# Scout-EasyEDA.net
KiCad netlist of a schematic drawn in EasyEDA
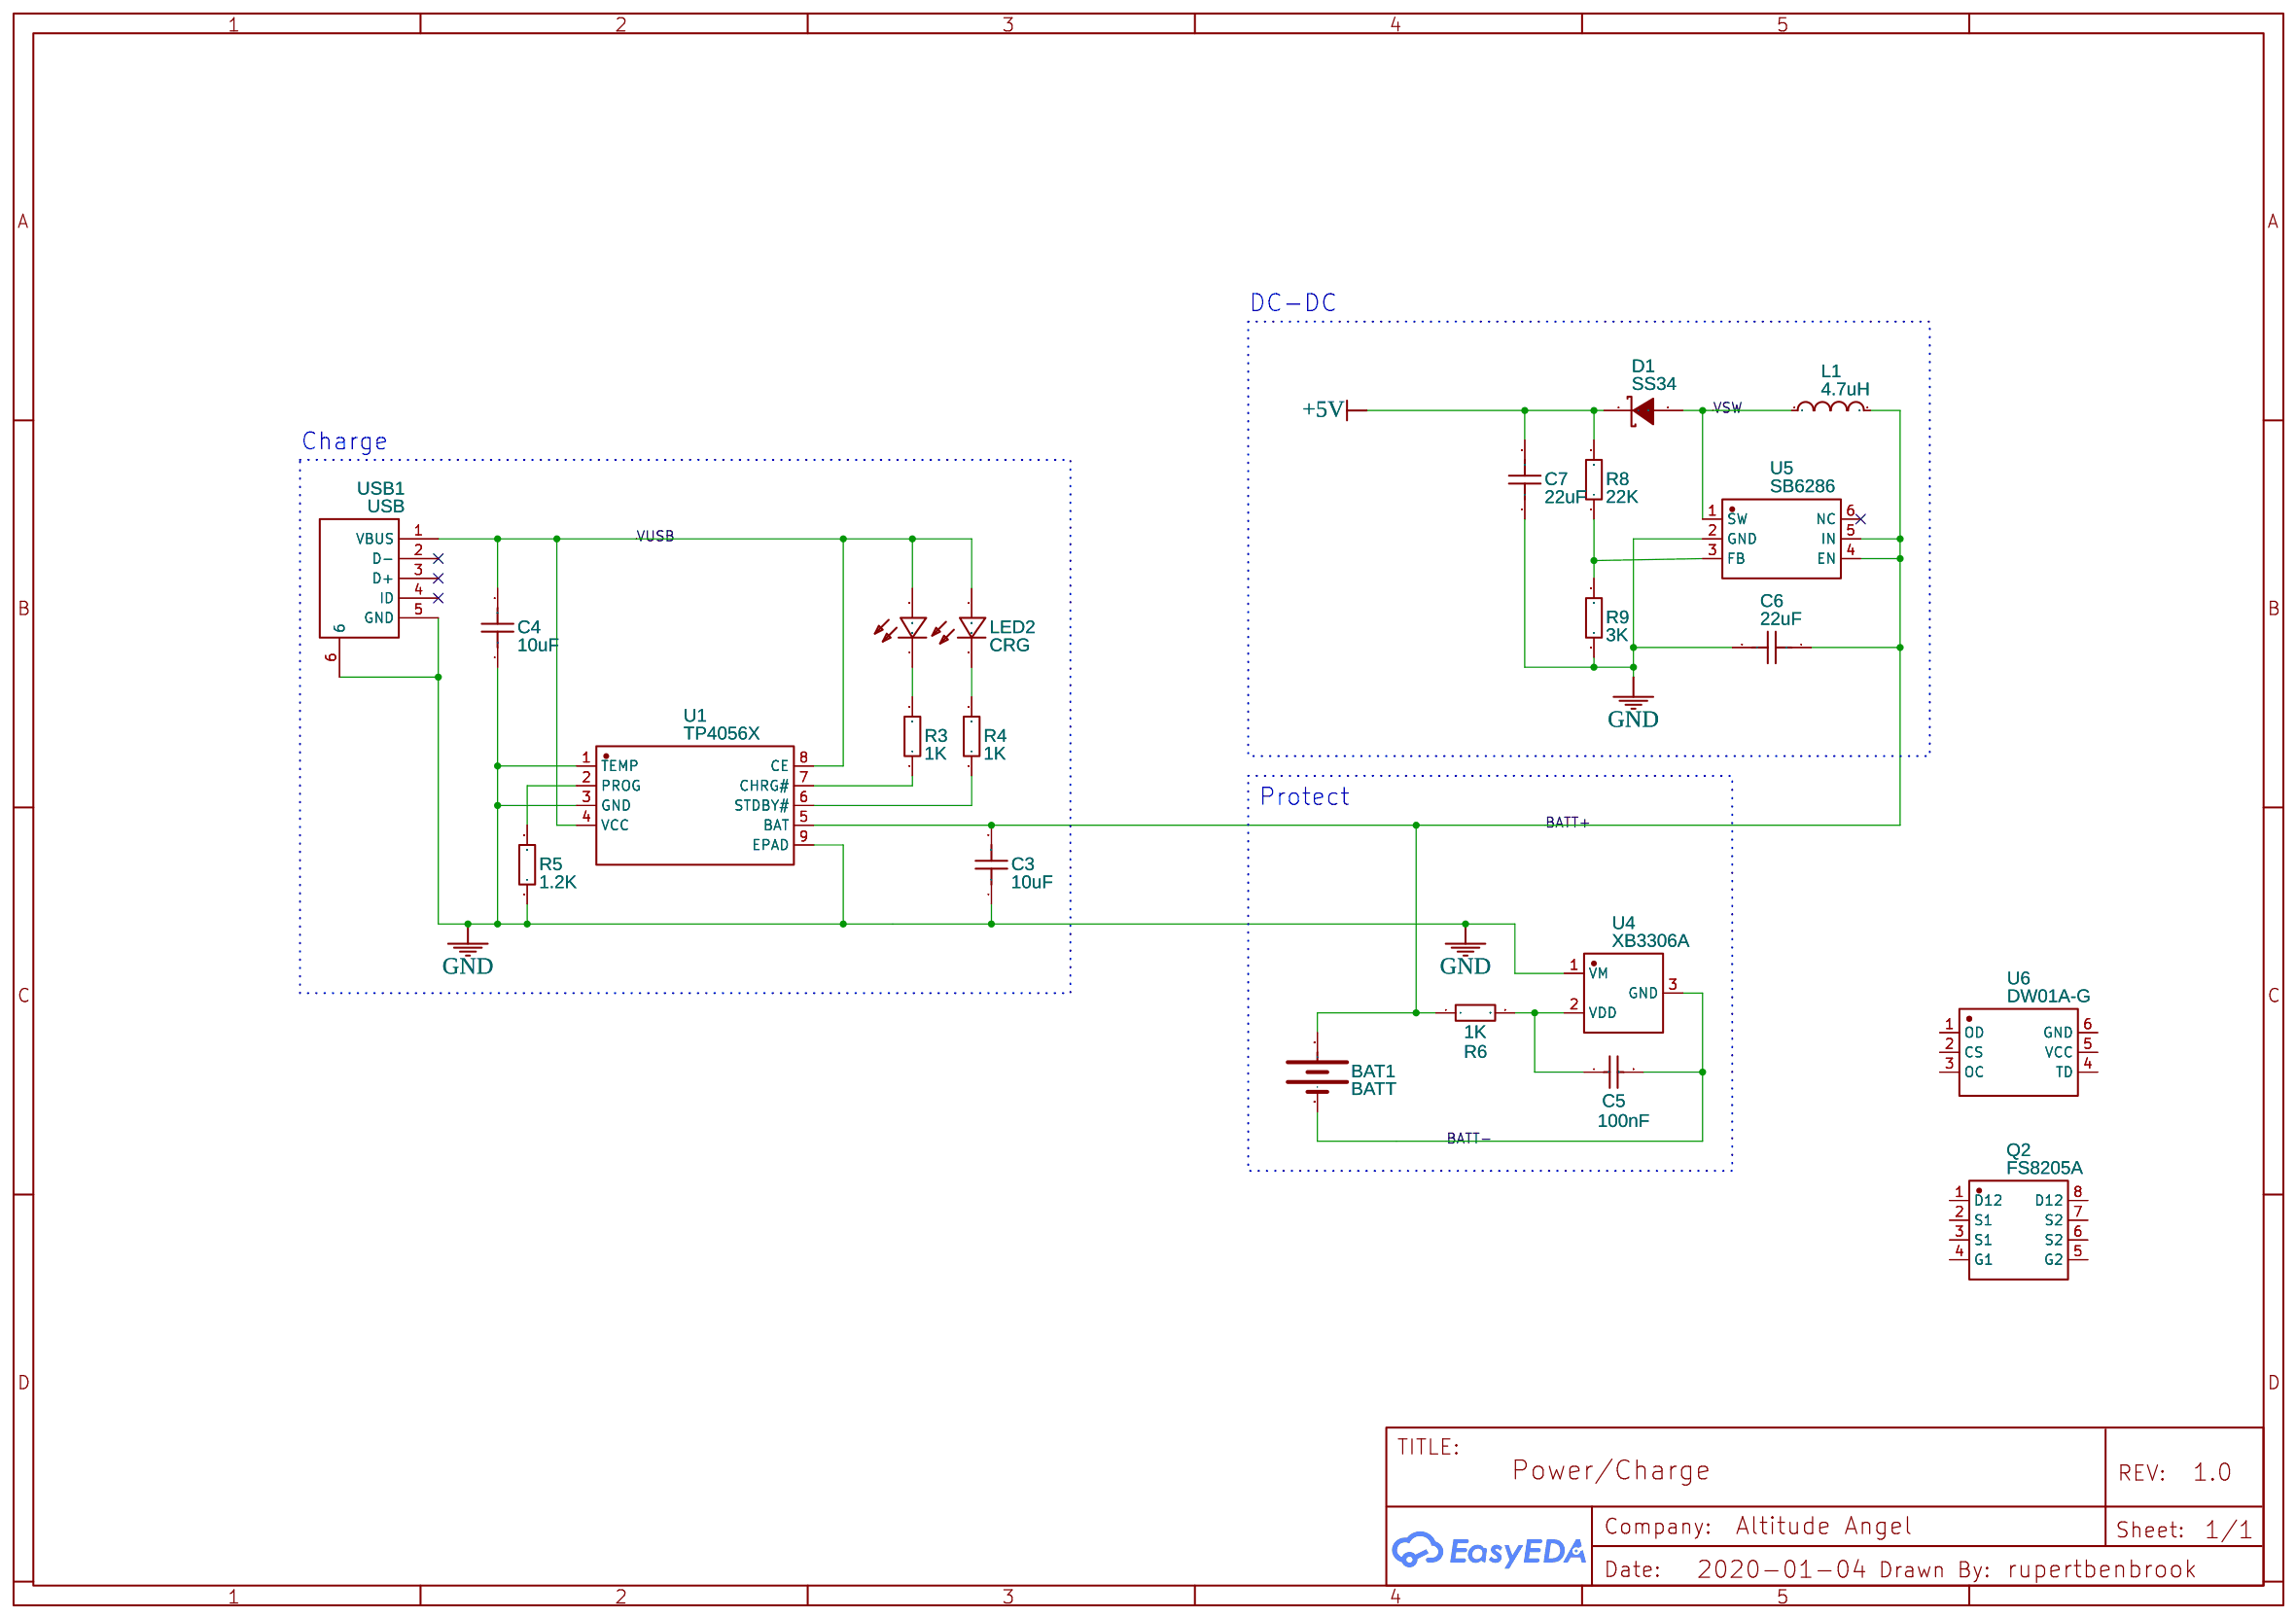
[diagram p0: Power-Charge]
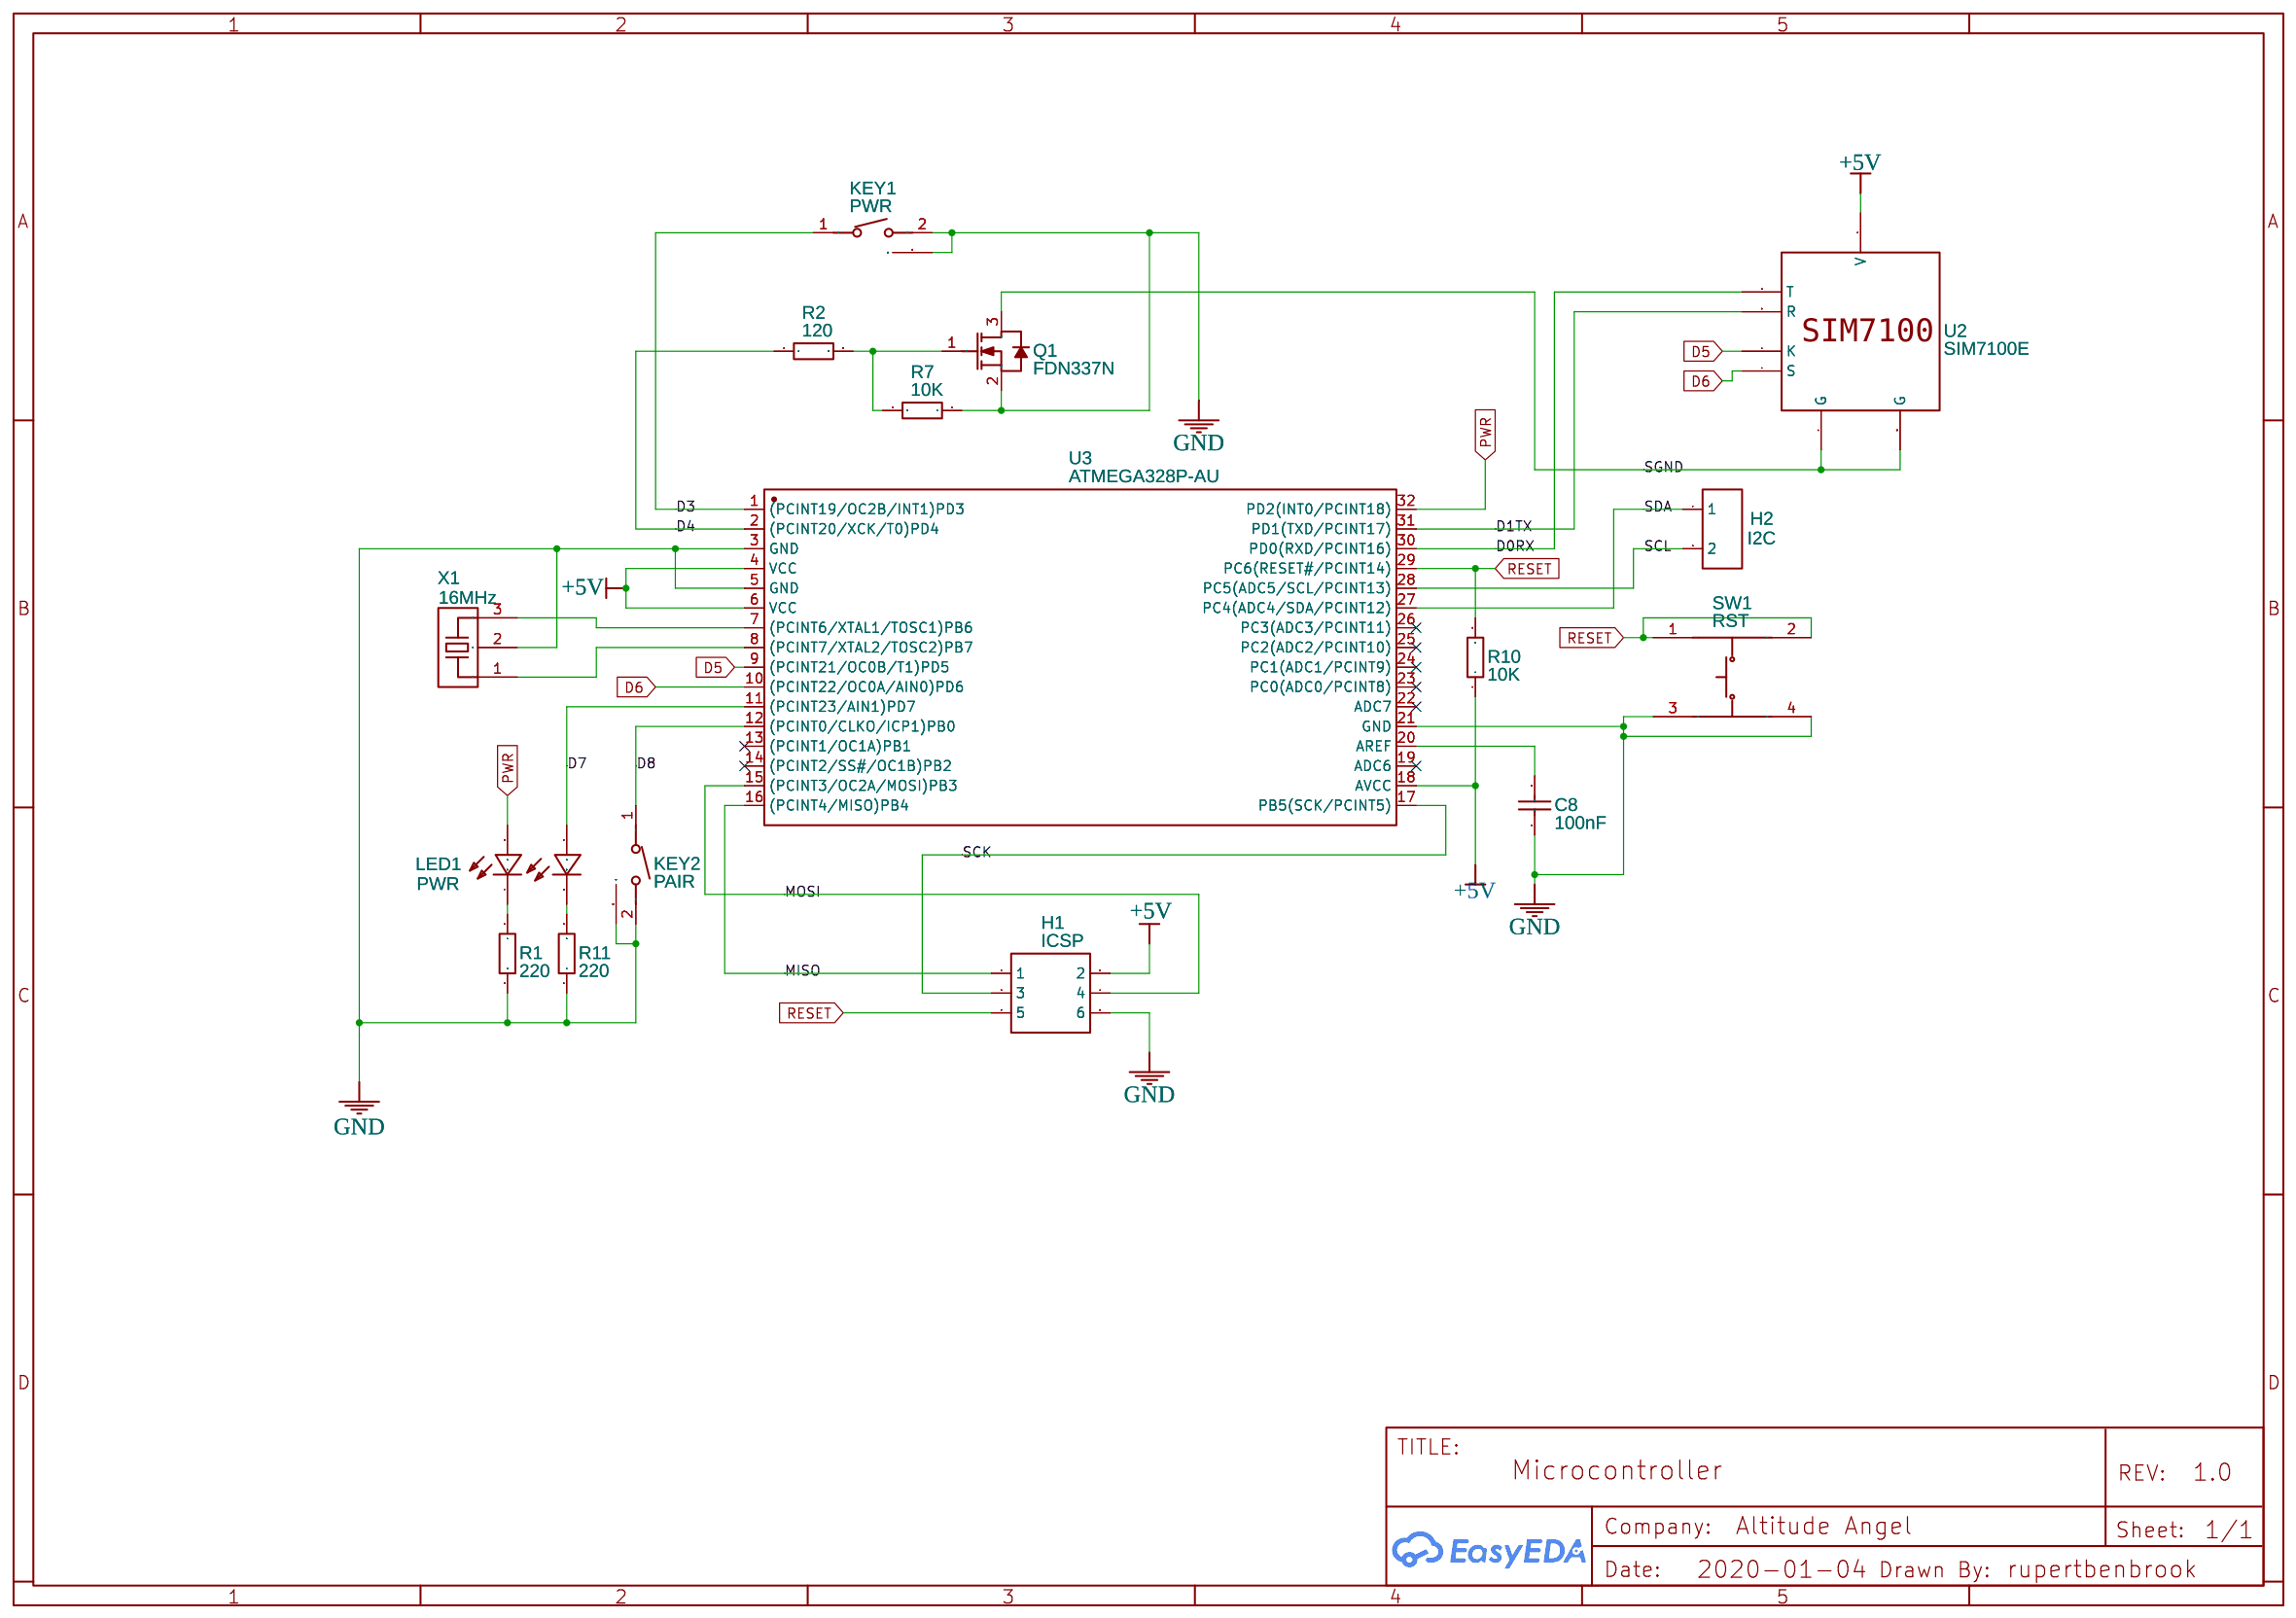
[diagram p1: Microcontroller]

(export (version "E")
  (design (tool "Eeschema 10.0.6"))
  (components
    (comp (ref "BAT1") (value "BATT") (libsource (lib "") (part "BATTERY18650")))
    (comp (ref "C3")
      (value "10uF")
      (fields
        (field (name "BOM_Manufacturer Part") "GRM188R61A106KE69D")
        (field (name "BOM_Supplier Part") "C77044")
      )
      (libsource (lib "") (part "GRM188R61A106KE69D"))
    )
    (comp (ref "C4")
      (value "10uF")
      (fields
        (field (name "BOM_Manufacturer Part") "GRM188R61A106KE69D")
        (field (name "BOM_Supplier Part") "C77044")
      )
      (libsource (lib "") (part "GRM188R61A106KE69D"))
    )
    (comp (ref "C5")
      (value "100nF")
      (fields
        (field (name "BOM_Manufacturer Part") "GRM188R71C104KA01D")
        (field (name "BOM_Supplier Part") "C45000")
      )
      (libsource (lib "") (part "GRM188R71C104KA01D"))
    )
    (comp (ref "C6")
      (value "22uF")
      (fields
        (field (name "BOM_Manufacturer Part") "GRM188R61A226ME15D")
        (field (name "BOM_Supplier Part") "C84419")
      )
      (libsource (lib "") (part "GRM188R61A226ME15D_1"))
    )
    (comp (ref "C7")
      (value "22uF")
      (fields
        (field (name "BOM_Manufacturer Part") "GRM188R61A226ME15D")
        (field (name "BOM_Supplier Part") "C84419")
      )
      (libsource (lib "") (part "GRM188R61A226ME15D"))
    )
    (comp (ref "D1")
      (value "SS34")
      (fields (field (name "BOM_Supplier Part") "C13762"))
      (libsource (lib "") (part "SS34_C13762"))
    )
    (comp (ref "L1")
      (value "4.7uH")
      (fields
        (field (name "BOM_Manufacturer Part") "LQH5BPN4R7NT0L")
        (field (name "BOM_Supplier Part") "C171792")
      )
      (libsource (lib "") (part "LQH5BPN4R7NT0L"))
    )
    (comp (ref "LED2")
      (value "CRG")
      (fields
        (field (name "BOM_Manufacturer Part") "LTST-C195KGJRKT")
        (field (name "BOM_Supplier Part") "C125104")
      )
      (libsource (lib "") (part "LTST-C195KGJRKT"))
    )
    (comp (ref "Q2")
      (value "FS8205A")
      (fields (field (name "BOM_Supplier Part") "C16052"))
      (libsource (lib "") (part "FS8205A"))
    )
    (comp (ref "R3")
      (value "1K")
      (fields
        (field (name "BOM_Manufacturer Part") "RTT031001FTP")
        (field (name "BOM_Supplier Part") "C103198")
      )
      (libsource (lib "") (part "RTT031001FTP"))
    )
    (comp (ref "R4")
      (value "1K")
      (fields
        (field (name "BOM_Manufacturer Part") "RTT031001FTP")
        (field (name "BOM_Supplier Part") "C103198")
      )
      (libsource (lib "") (part "RTT031001FTP"))
    )
    (comp (ref "R5")
      (value "1.2K")
      (fields
        (field (name "BOM_Manufacturer Part") "RTT031201FTP")
        (field (name "BOM_Supplier Part") "C103248")
      )
      (libsource (lib "") (part "RTT031201FTP"))
    )
    (comp (ref "R6")
      (value "1K")
      (fields
        (field (name "BOM_Manufacturer Part") "RTT031001FTP")
        (field (name "BOM_Supplier Part") "C103198")
      )
      (libsource (lib "") (part "RTT031001FTP_1"))
    )
    (comp (ref "R8")
      (value "22K")
      (fields
        (field (name "BOM_Manufacturer Part") "RTT032202FTP")
        (field (name "BOM_Supplier Part") "C103416")
      )
      (libsource (lib "") (part "RTT032202FTP"))
    )
    (comp (ref "R9")
      (value "3K")
      (fields
        (field (name "BOM_Manufacturer Part") "RTT033001FTP")
        (field (name "BOM_Supplier Part") "C103514")
      )
      (libsource (lib "") (part "RTT033001FTP"))
    )
    (comp (ref "U1")
      (value "TP4056X")
      (fields (field (name "BOM_Supplier Part") "C191323"))
      (libsource (lib "") (part "TP4056X"))
    )
    (comp (ref "U4")
      (value "XB3306A")
      (fields (field (name "BOM_Supplier Part") "C154939"))
      (libsource (lib "") (part "XB3306A"))
    )
    (comp (ref "U5")
      (value "SB6286")
      (fields (field (name "BOM_Supplier Part") "C157668"))
      (libsource (lib "") (part "SB6286"))
    )
    (comp (ref "U6")
      (value "DW01A-G")
      (fields (field (name "BOM_Supplier Part") "C61503"))
      (libsource (lib "") (part "DW01A-G"))
    )
    (comp (ref "USB1")
      (value "USB")
      (fields
        (field (name "BOM_Manufacturer Part") "MICRO5.9mmusb")
        (field (name "BOM_Supplier Part") "C393940")
      )
      (libsource (lib "") (part "MICRO5.9MMUSB"))
    )
    (comp (ref "C8")
      (value "100nF")
      (fields
        (field (name "BOM_Manufacturer Part") "GRM188R71C104KA01D")
        (field (name "BOM_Supplier Part") "C45000")
      )
      (libsource (lib "") (part "GRM188R71C104KA01D"))
    )
    (comp (ref "H1")
      (value "ICSP")
      (fields
        (field (name "BOM_Manufacturer Part") "Header-Male-2.54_2x3")
        (field (name "BOM_Supplier Part") "C65114")
      )
      (libsource (lib "") (part "Header-Male-2.54_2x3"))
    )
    (comp (ref "H2")
      (value "I2C")
      (fields (field (name "BOM_Manufacturer Part") "826629-2") (field (name "BOM_Supplier Part") "C86471"))
      (libsource (lib "") (part "Header-Male-2.54_1x2"))
    )
    (comp (ref "KEY1")
      (value "PWR")
      (fields
        (field (name "BOM_Manufacturer Part") "KAN4562-0501C")
        (field (name "BOM_Supplier Part") "C231728")
      )
      (libsource (lib "") (part "KAN4562-0501C_1"))
    )
    (comp (ref "KEY2")
      (value "PAIR")
      (fields
        (field (name "BOM_Manufacturer Part") "KAN4562-0501C")
        (field (name "BOM_Supplier Part") "C231728")
      )
      (libsource (lib "") (part "KAN4562-0501C"))
    )
    (comp (ref "LED1")
      (value "PWR")
      (fields
        (field (name "BOM_Manufacturer Part") "LTST-C195KGJRKT")
        (field (name "BOM_Supplier Part") "C125104")
      )
      (libsource (lib "") (part "LTST-C195KGJRKT"))
    )
    (comp (ref "Q1")
      (value "FDN337N")
      (fields (field (name "BOM_Supplier Part") "C241805"))
      (libsource (lib "") (part "FDN337N"))
    )
    (comp (ref "R1")
      (value "220")
      (fields
        (field (name "BOM_Manufacturer Part") "RTT032200FTP")
        (field (name "BOM_Supplier Part") "C103414")
      )
      (libsource (lib "") (part "RTT032200FTP_1"))
    )
    (comp (ref "R2")
      (value "120")
      (fields
        (field (name "BOM_Manufacturer Part") "RTT031200FTP")
        (field (name "BOM_Supplier Part") "C103247")
      )
      (libsource (lib "") (part "RTT031200FTP"))
    )
    (comp (ref "R7")
      (value "10K")
      (fields
        (field (name "BOM_Manufacturer Part") "RTT031002FTP")
        (field (name "BOM_Supplier Part") "C103199")
      )
      (libsource (lib "") (part "RTT031002FTP_1"))
    )
    (comp (ref "R10")
      (value "10K")
      (fields
        (field (name "BOM_Manufacturer Part") "RTT031002FTP")
        (field (name "BOM_Supplier Part") "C103199")
      )
      (libsource (lib "") (part "RTT031002FTP"))
    )
    (comp (ref "R11")
      (value "220")
      (fields
        (field (name "BOM_Manufacturer Part") "RTT032200FTP")
        (field (name "BOM_Supplier Part") "C103414")
      )
      (libsource (lib "") (part "RTT032200FTP"))
    )
    (comp (ref "SW1")
      (value "RST")
      (fields
        (field (name "BOM_Manufacturer Part") "TS-1177-B-A-B")
        (field (name "BOM_Supplier Part") "C381051")
      )
      (libsource (lib "") (part "TS-1177-B-A-B"))
    )
    (comp (ref "U2")
      (value "SIM7100E")
      (fields (field (name "BOM_Manufacturer Part") "SIM808"))
      (libsource (lib "") (part "SIM7100E"))
    )
    (comp (ref "U3")
      (value "ATMEGA328P-AU")
      (fields (field (name "BOM_Supplier Part") "C14877"))
      (libsource (lib "") (part "ATMEGA328P-AU"))
    )
    (comp (ref "X1")
      (value "16MHz")
      (fields
        (field (name "BOM_Manufacturer Part") "CSTCE16M0V53-R0")
        (field (name "BOM_Supplier Part") "C32180")
      )
      (libsource (lib "") (part "CSTCE16M0V53-R0"))
    )
  )
  (nets
    (net (code "1") (name "+5V") (class "Default")
      (node (ref "C7") (pin "2") (pinfunction "2_2") (pintype "unspecified"))
      (node (ref "D1") (pin "2") (pinfunction "K_2") (pintype "unspecified"))
      (node (ref "H1") (pin "2") (pinfunction "2_2") (pintype "input"))
      (node (ref "R10") (pin "1") (pinfunction "1_1") (pintype "input"))
      (node (ref "R8") (pin "2") (pinfunction "2_2") (pintype "input"))
      (node (ref "U2") (pin "5") (pinfunction "V_5") (pintype "unspecified"))
      (node (ref "U3") (pin "18") (pinfunction "AVCC_18") (pintype "unspecified"))
      (node (ref "U3") (pin "4") (pinfunction "VCC_4") (pintype "unspecified"))
      (node (ref "U3") (pin "6") (pinfunction "VCC_6") (pintype "unspecified"))
    )
    (net (code "2") (name "BATT+") (class "Default")
      (node (ref "BAT1") (pin "PWR") (pinfunction "+_PWR") (pintype "passive"))
      (node (ref "C3") (pin "2") (pinfunction "2_2") (pintype "unspecified"))
      (node (ref "C6") (pin "1") (pinfunction "1_1") (pintype "unspecified"))
      (node (ref "L1") (pin "2") (pinfunction "2_2") (pintype "unspecified"))
      (node (ref "R6") (pin "1") (pinfunction "1_1") (pintype "input"))
      (node (ref "U1") (pin "5") (pinfunction "BAT_5") (pintype "unspecified"))
      (node (ref "U5") (pin "4") (pinfunction "EN_4") (pintype "unspecified"))
      (node (ref "U5") (pin "5") (pinfunction "IN_5") (pintype "unspecified"))
    )
    (net (code "3") (name "BATT-") (class "Default")
      (node (ref "BAT1") (pin "GND") (pinfunction "-_GND") (pintype "passive"))
      (node (ref "C5") (pin "2") (pinfunction "2_2") (pintype "input"))
      (node (ref "U4") (pin "3") (pinfunction "GND_3") (pintype "unspecified"))
    )
    (net (code "4") (name "D0RX") (class "Default")
      (node (ref "U2") (pin "3") (pinfunction "T_3") (pintype "unspecified"))
      (node (ref "U3") (pin "30") (pinfunction "PD0(RXD/PCINT16)_30") (pintype "unspecified"))
    )
    (net (code "5") (name "D1TX") (class "Default")
      (node (ref "U2") (pin "2") (pinfunction "R_2") (pintype "unspecified"))
      (node (ref "U3") (pin "31") (pinfunction "PD1(TXD/PCINT17)_31") (pintype "unspecified"))
    )
    (net (code "6") (name "D3") (class "Default")
      (node (ref "KEY1") (pin "1") (pinfunction "1_1") (pintype "input"))
      (node (ref "U3") (pin "1") (pinfunction "(PCINT19/OC2B/INT1)PD3_1") (pintype "unspecified"))
    )
    (net (code "7") (name "D4") (class "Default")
      (node (ref "R2") (pin "1") (pinfunction "1_1") (pintype "input"))
      (node (ref "U3") (pin "2") (pinfunction "(PCINT20/XCK/T0)PD4_2") (pintype "unspecified"))
    )
    (net (code "8") (name "D5") (class "Default")
      (node (ref "U2") (pin "4") (pinfunction "K_4") (pintype "unspecified"))
      (node (ref "U3") (pin "9") (pinfunction "(PCINT21/OC0B/T1)PD5_9") (pintype "unspecified"))
    )
    (net (code "9") (name "D6") (class "Default")
      (node (ref "U2") (pin "7") (pinfunction "S_7") (pintype "unspecified"))
      (node (ref "U3") (pin "10") (pinfunction "(PCINT22/OC0A/AIN0)PD6_10") (pintype "unspecified"))
    )
    (net (code "10") (name "D7") (class "Default")
      (node (ref "LED1") (pin "1") (pinfunction "G+_1") (pintype "unspecified"))
      (node (ref "U3") (pin "11") (pinfunction "(PCINT23/AIN1)PD7_11") (pintype "unspecified"))
    )
    (net (code "11") (name "D8") (class "Default")
      (node (ref "KEY2") (pin "1") (pinfunction "1_1") (pintype "input"))
      (node (ref "U3") (pin "12") (pinfunction "(PCINT0/CLKO/ICP1)PB0_12") (pintype "unspecified"))
    )
    (net (code "12") (name "GND") (class "Default")
      (node (ref "C3") (pin "1") (pinfunction "1_1") (pintype "unspecified"))
      (node (ref "C4") (pin "1") (pinfunction "1_1") (pintype "unspecified"))
      (node (ref "C6") (pin "2") (pinfunction "2_2") (pintype "unspecified"))
      (node (ref "C7") (pin "1") (pinfunction "1_1") (pintype "unspecified"))
      (node (ref "C8") (pin "1") (pinfunction "1_1") (pintype "input"))
      (node (ref "H1") (pin "6") (pinfunction "6_6") (pintype "input"))
      (node (ref "KEY1") (pin "0") (pinfunction "0_0") (pintype "input"))
      (node (ref "KEY1") (pin "2") (pinfunction "2_2") (pintype "input"))
      (node (ref "KEY2") (pin "0") (pinfunction "0_0") (pintype "input"))
      (node (ref "KEY2") (pin "2") (pinfunction "2_2") (pintype "input"))
      (node (ref "Q1") (pin "2") (pinfunction "S_2") (pintype "unspecified"))
      (node (ref "R1") (pin "2") (pinfunction "2_2") (pintype "input"))
      (node (ref "R11") (pin "1") (pinfunction "1_1") (pintype "input"))
      (node (ref "R5") (pin "1") (pinfunction "1_1") (pintype "input"))
      (node (ref "R7") (pin "1") (pinfunction "1_1") (pintype "input"))
      (node (ref "R9") (pin "1") (pinfunction "1_1") (pintype "input"))
      (node (ref "SW1") (pin "3") (pinfunction "3_3") (pintype "unspecified"))
      (node (ref "SW1") (pin "4") (pinfunction "4_4") (pintype "unspecified"))
      (node (ref "U1") (pin "1") (pinfunction "TEMP_1") (pintype "unspecified"))
      (node (ref "U1") (pin "3") (pinfunction "GND_3") (pintype "unspecified"))
      (node (ref "U1") (pin "9") (pinfunction "EPAD_9") (pintype "unspecified"))
      (node (ref "U3") (pin "21") (pinfunction "GND_21") (pintype "unspecified"))
      (node (ref "U3") (pin "3") (pinfunction "GND_3") (pintype "unspecified"))
      (node (ref "U3") (pin "5") (pinfunction "GND_5") (pintype "unspecified"))
      (node (ref "U4") (pin "1") (pinfunction "VM_1") (pintype "unspecified"))
      (node (ref "U5") (pin "2") (pinfunction "GND_2") (pintype "unspecified"))
      (node (ref "USB1") (pin "5") (pinfunction "GND_5") (pintype "unspecified"))
      (node (ref "USB1") (pin "6") (pinfunction "6_6") (pintype "unspecified"))
      (node (ref "X1") (pin "2") (pinfunction "2_2") (pintype "unspecified"))
    )
    (net (code "13") (name "MISO") (class "Default")
      (node (ref "H1") (pin "1") (pinfunction "1_1") (pintype "input"))
      (node (ref "U3") (pin "16") (pinfunction "(PCINT4/MISO)PB4_16") (pintype "unspecified"))
    )
    (net (code "14") (name "MOSI") (class "Default")
      (node (ref "H1") (pin "4") (pinfunction "4_4") (pintype "input"))
      (node (ref "U3") (pin "15") (pinfunction "(PCINT3/OC2A/MOSI)PB3_15") (pintype "unspecified"))
    )
    (net (code "15") (name "Net-(LED1-G-)") (class "Default")
      (node (ref "LED1") (pin "3") (pinfunction "G-_3") (pintype "unspecified"))
      (node (ref "R11") (pin "2") (pinfunction "2_2") (pintype "input"))
    )
    (net (code "16") (name "Net-(LED1-R-)") (class "Default")
      (node (ref "LED1") (pin "4") (pinfunction "R-_4") (pintype "unspecified"))
      (node (ref "R1") (pin "1") (pinfunction "1_1") (pintype "input"))
    )
    (net (code "17") (name "Net-(LED2-G-)") (class "Default")
      (node (ref "LED2") (pin "3") (pinfunction "G-_3") (pintype "unspecified"))
      (node (ref "R4") (pin "2") (pinfunction "2_2") (pintype "input"))
    )
    (net (code "18") (name "Net-(LED2-R-)") (class "Default")
      (node (ref "LED2") (pin "4") (pinfunction "R-_4") (pintype "unspecified"))
      (node (ref "R3") (pin "2") (pinfunction "2_2") (pintype "input"))
    )
    (net (code "19") (name "Net-(Q1-G)") (class "Default")
      (node (ref "Q1") (pin "1") (pinfunction "G_1") (pintype "unspecified"))
      (node (ref "R2") (pin "2") (pinfunction "2_2") (pintype "input"))
      (node (ref "R7") (pin "2") (pinfunction "2_2") (pintype "input"))
    )
    (net (code "20") (name "Net-(U1-CHRG#)") (class "Default")
      (node (ref "R3") (pin "1") (pinfunction "1_1") (pintype "input"))
      (node (ref "U1") (pin "7") (pinfunction "CHRG#_7") (pintype "unspecified"))
    )
    (net (code "21") (name "Net-(U1-PROG)") (class "Default")
      (node (ref "R5") (pin "2") (pinfunction "2_2") (pintype "input"))
      (node (ref "U1") (pin "2") (pinfunction "PROG_2") (pintype "unspecified"))
    )
    (net (code "22") (name "Net-(U1-STDBY#)") (class "Default")
      (node (ref "R4") (pin "1") (pinfunction "1_1") (pintype "input"))
      (node (ref "U1") (pin "6") (pinfunction "STDBY#_6") (pintype "unspecified"))
    )
    (net (code "23") (name "Net-(U3-(PCINT6{slash}XTAL1{slash}TOSC1)PB6)") (class "Default")
      (node (ref "U3") (pin "7") (pinfunction "(PCINT6/XTAL1/TOSC1)PB6_7") (pintype "unspecified"))
      (node (ref "X1") (pin "3") (pinfunction "3_3") (pintype "unspecified"))
    )
    (net (code "24") (name "Net-(U3-(PCINT7{slash}XTAL2{slash}TOSC2)PB7)") (class "Default")
      (node (ref "U3") (pin "8") (pinfunction "(PCINT7/XTAL2/TOSC2)PB7_8") (pintype "unspecified"))
      (node (ref "X1") (pin "1") (pinfunction "1_1") (pintype "unspecified"))
    )
    (net (code "25") (name "Net-(U3-AREF)") (class "Default")
      (node (ref "C8") (pin "2") (pinfunction "2_2") (pintype "input"))
      (node (ref "U3") (pin "20") (pinfunction "AREF_20") (pintype "unspecified"))
    )
    (net (code "26") (name "Net-(U4-VDD)") (class "Default")
      (node (ref "C5") (pin "1") (pinfunction "1_1") (pintype "input"))
      (node (ref "R6") (pin "2") (pinfunction "2_2") (pintype "input"))
      (node (ref "U4") (pin "2") (pinfunction "VDD_2") (pintype "unspecified"))
    )
    (net (code "27") (name "Net-(U5-FB)") (class "Default")
      (node (ref "R8") (pin "1") (pinfunction "1_1") (pintype "input"))
      (node (ref "R9") (pin "2") (pinfunction "2_2") (pintype "input"))
      (node (ref "U5") (pin "3") (pinfunction "FB_3") (pintype "unspecified"))
    )
    (net (code "28") (name "PWR") (class "Default")
      (node (ref "LED1") (pin "2") (pinfunction "R+_2") (pintype "unspecified"))
      (node (ref "U3") (pin "32") (pinfunction "PD2(INT0/PCINT18)_32") (pintype "unspecified"))
    )
    (net (code "29") (name "RESET") (class "Default")
      (node (ref "H1") (pin "5") (pinfunction "5_5") (pintype "input"))
      (node (ref "R10") (pin "2") (pinfunction "2_2") (pintype "input"))
      (node (ref "SW1") (pin "1") (pinfunction "1_1") (pintype "unspecified"))
      (node (ref "SW1") (pin "2") (pinfunction "2_2") (pintype "unspecified"))
      (node (ref "U3") (pin "29") (pinfunction "PC6(RESET#/PCINT14)_29") (pintype "unspecified"))
    )
    (net (code "30") (name "SCK") (class "Default")
      (node (ref "H1") (pin "3") (pinfunction "3_3") (pintype "input"))
      (node (ref "U3") (pin "17") (pinfunction "PB5(SCK/PCINT5)_17") (pintype "unspecified"))
    )
    (net (code "31") (name "SCL") (class "Default")
      (node (ref "H2") (pin "2") (pinfunction "2_2") (pintype "unspecified"))
      (node (ref "U3") (pin "28") (pinfunction "PC5(ADC5/SCL/PCINT13)_28") (pintype "unspecified"))
    )
    (net (code "32") (name "SDA") (class "Default")
      (node (ref "H2") (pin "1") (pinfunction "1_1") (pintype "unspecified"))
      (node (ref "U3") (pin "27") (pinfunction "PC4(ADC4/SDA/PCINT12)_27") (pintype "unspecified"))
    )
    (net (code "33") (name "SGND") (class "Default")
      (node (ref "Q1") (pin "3") (pinfunction "D_3") (pintype "unspecified"))
      (node (ref "U2") (pin "1") (pinfunction "G_1") (pintype "unspecified"))
      (node (ref "U2") (pin "6") (pinfunction "G_6") (pintype "unspecified"))
    )
    (net (code "34") (name "VSW") (class "Default")
      (node (ref "D1") (pin "1") (pinfunction "A_1") (pintype "unspecified"))
      (node (ref "L1") (pin "1") (pinfunction "1_1") (pintype "unspecified"))
      (node (ref "U5") (pin "1") (pinfunction "SW_1") (pintype "unspecified"))
    )
    (net (code "35") (name "VUSB") (class "Default")
      (node (ref "C4") (pin "2") (pinfunction "2_2") (pintype "unspecified"))
      (node (ref "LED2") (pin "1") (pinfunction "G+_1") (pintype "unspecified"))
      (node (ref "LED2") (pin "2") (pinfunction "R+_2") (pintype "unspecified"))
      (node (ref "U1") (pin "4") (pinfunction "VCC_4") (pintype "unspecified"))
      (node (ref "U1") (pin "8") (pinfunction "CE_8") (pintype "unspecified"))
      (node (ref "USB1") (pin "1") (pinfunction "VBUS_1") (pintype "unspecified"))
    )
    (net (code "36") (name "unconnected-(Q2-D12-Pad1)") (class "Default")
      (node (ref "Q2") (pin "1") (pinfunction "D12_1") (pintype "unspecified"))
    )
    (net (code "37") (name "unconnected-(Q2-D12-Pad8)") (class "Default")
      (node (ref "Q2") (pin "8") (pinfunction "D12_8") (pintype "unspecified"))
    )
    (net (code "38") (name "unconnected-(Q2-G1-Pad4)") (class "Default")
      (node (ref "Q2") (pin "4") (pinfunction "G1_4") (pintype "unspecified"))
    )
    (net (code "39") (name "unconnected-(Q2-G2-Pad5)") (class "Default")
      (node (ref "Q2") (pin "5") (pinfunction "G2_5") (pintype "unspecified"))
    )
    (net (code "40") (name "unconnected-(Q2-S1-Pad2)") (class "Default")
      (node (ref "Q2") (pin "2") (pinfunction "S1_2") (pintype "unspecified"))
    )
    (net (code "41") (name "unconnected-(Q2-S1-Pad3)") (class "Default")
      (node (ref "Q2") (pin "3") (pinfunction "S1_3") (pintype "unspecified"))
    )
    (net (code "42") (name "unconnected-(Q2-S2-Pad6)") (class "Default")
      (node (ref "Q2") (pin "6") (pinfunction "S2_6") (pintype "unspecified"))
    )
    (net (code "43") (name "unconnected-(Q2-S2-Pad7)") (class "Default")
      (node (ref "Q2") (pin "7") (pinfunction "S2_7") (pintype "unspecified"))
    )
    (net (code "44") (name "unconnected-(U3-(PCINT1{slash}OC1A)PB1-Pad13)") (class "Default")
      (node (ref "U3") (pin "13") (pinfunction "(PCINT1/OC1A)PB1_13") (pintype "unspecified+no_connect"))
    )
    (net (code "45") (name "unconnected-(U3-(PCINT2{slash}SS#{slash}OC1B)PB2-Pad14)") (class "Default")
      (node (ref "U3") (pin "14") (pinfunction "(PCINT2/SS#/OC1B)PB2_14") (pintype "unspecified+no_connect"))
    )
    (net (code "46") (name "unconnected-(U3-ADC6-Pad19)") (class "Default")
      (node (ref "U3") (pin "19") (pinfunction "ADC6_19") (pintype "unspecified+no_connect"))
    )
    (net (code "47") (name "unconnected-(U3-ADC7-Pad22)") (class "Default")
      (node (ref "U3") (pin "22") (pinfunction "ADC7_22") (pintype "unspecified+no_connect"))
    )
    (net (code "48") (name "unconnected-(U3-PC0(ADC0{slash}PCINT8)-Pad23)") (class "Default")
      (node (ref "U3") (pin "23") (pinfunction "PC0(ADC0/PCINT8)_23") (pintype "unspecified+no_connect"))
    )
    (net (code "49") (name "unconnected-(U3-PC1(ADC1{slash}PCINT9)-Pad24)") (class "Default")
      (node (ref "U3") (pin "24") (pinfunction "PC1(ADC1/PCINT9)_24") (pintype "unspecified+no_connect"))
    )
    (net (code "50") (name "unconnected-(U3-PC2(ADC2{slash}PCINT10)-Pad25)") (class "Default")
      (node (ref "U3") (pin "25") (pinfunction "PC2(ADC2/PCINT10)_25") (pintype "unspecified+no_connect"))
    )
    (net (code "51") (name "unconnected-(U3-PC3(ADC3{slash}PCINT11)-Pad26)") (class "Default")
      (node (ref "U3") (pin "26") (pinfunction "PC3(ADC3/PCINT11)_26") (pintype "unspecified+no_connect"))
    )
    (net (code "52") (name "unconnected-(U5-NC-Pad6)") (class "Default")
      (node (ref "U5") (pin "6") (pinfunction "NC_6") (pintype "unspecified+no_connect"))
    )
    (net (code "53") (name "unconnected-(U6-CS-Pad2)") (class "Default")
      (node (ref "U6") (pin "2") (pinfunction "CS_2") (pintype "unspecified"))
    )
    (net (code "54") (name "unconnected-(U6-GND-Pad6)") (class "Default")
      (node (ref "U6") (pin "6") (pinfunction "GND_6") (pintype "unspecified"))
    )
    (net (code "55") (name "unconnected-(U6-OC-Pad3)") (class "Default")
      (node (ref "U6") (pin "3") (pinfunction "OC_3") (pintype "unspecified"))
    )
    (net (code "56") (name "unconnected-(U6-OD-Pad1)") (class "Default")
      (node (ref "U6") (pin "1") (pinfunction "OD_1") (pintype "unspecified"))
    )
    (net (code "57") (name "unconnected-(U6-TD-Pad4)") (class "Default")
      (node (ref "U6") (pin "4") (pinfunction "TD_4") (pintype "unspecified"))
    )
    (net (code "58") (name "unconnected-(U6-VCC-Pad5)") (class "Default")
      (node (ref "U6") (pin "5") (pinfunction "VCC_5") (pintype "unspecified"))
    )
    (net (code "59") (name "unconnected-(USB1-D+-Pad3)") (class "Default")
      (node (ref "USB1") (pin "3") (pinfunction "D+_3") (pintype "unspecified+no_connect"))
    )
    (net (code "60") (name "unconnected-(USB1-D--Pad2)") (class "Default")
      (node (ref "USB1") (pin "2") (pinfunction "D-_2") (pintype "unspecified+no_connect"))
    )
    (net (code "61") (name "unconnected-(USB1-ID-Pad4)") (class "Default")
      (node (ref "USB1") (pin "4") (pinfunction "ID_4") (pintype "unspecified+no_connect"))
    )
  )
)
